# AD637-.net
KiCad netlist of a schematic drawn in Altium Designer
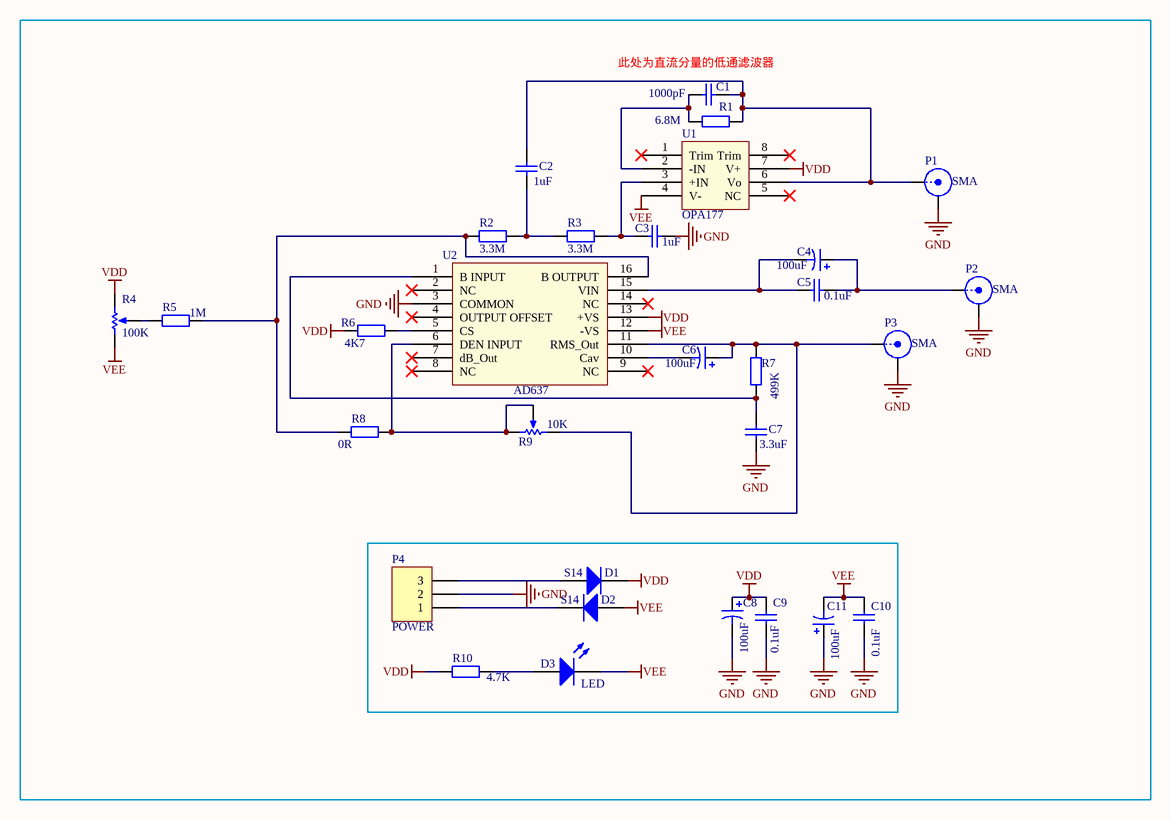
[diagram p0: AD637-有效值检测新版.SchDoc]

(export (version "E")
  (design (tool "Eeschema 10.0.6"))
  (components
    (comp (ref "C1")
      (value "1000pF")
      (footprint "common:C0805")
      (description "Capacitor")
      (fields (field (name "PUBLISHER") "Altium Limited"))
      (libsource (lib "Miscellaneous Devices") (part "Cap"))
    )
    (comp (ref "C2")
      (value "1uF")
      (footprint "common:C0805")
      (description "Capacitor")
      (fields (field (name "PUBLISHER") "Altium Limited"))
      (libsource (lib "Miscellaneous Devices") (part "Cap"))
    )
    (comp (ref "C3")
      (value "1uF")
      (footprint "common:C0805")
      (description "Capacitor")
      (fields (field (name "PUBLISHER") "Altium Limited"))
      (libsource (lib "Miscellaneous Devices") (part "Cap"))
    )
    (comp (ref "C4")
      (value "100uF")
      (footprint "common:C7343")
      (description "Polarized Capacitor (Radial)")
      (fields (field (name "PUBLISHER") "Altium Limited"))
      (libsource (lib "Miscellaneous Devices") (part "Cap Pol1"))
    )
    (comp (ref "C5")
      (value "0.1uF")
      (footprint "common:C0805")
      (description "Capacitor")
      (fields (field (name "PUBLISHER") "Altium Limited"))
      (libsource (lib "Miscellaneous Devices") (part "Cap"))
    )
    (comp (ref "C6")
      (value "100uF")
      (footprint "common:C7343")
      (description "Polarized Capacitor (Radial)")
      (fields (field (name "PUBLISHER") "Altium Limited"))
      (libsource (lib "Miscellaneous Devices") (part "Cap Pol1"))
    )
    (comp (ref "C7")
      (value "3.3uF")
      (footprint "common:C0805")
      (description "Capacitor")
      (fields (field (name "PUBLISHER") "Altium Limited"))
      (libsource (lib "Miscellaneous Devices") (part "Cap"))
    )
    (comp (ref "C8")
      (value "100uF")
      (footprint "common:C7343")
      (description "Polarized Capacitor (Radial)")
      (fields (field (name "PUBLISHER") "Altium Limited"))
      (libsource (lib "Miscellaneous Devices") (part "Cap Pol1"))
    )
    (comp (ref "C9")
      (value "0.1uF")
      (footprint "common:C0805")
      (description "Capacitor")
      (fields (field (name "PUBLISHER") "Altium Limited"))
      (libsource (lib "Miscellaneous Devices") (part "Cap"))
    )
    (comp (ref "C10")
      (value "0.1uF")
      (footprint "common:C0805")
      (description "Capacitor")
      (fields (field (name "PUBLISHER") "Altium Limited"))
      (libsource (lib "Miscellaneous Devices") (part "Cap"))
    )
    (comp (ref "C11")
      (value "100uF")
      (footprint "common:C7343")
      (description "Polarized Capacitor (Radial)")
      (fields (field (name "PUBLISHER") "Altium Limited"))
      (libsource (lib "Miscellaneous Devices") (part "Cap Pol1"))
    )
    (comp (ref "D1")
      (value "S14")
      (footprint "common:SOD123")
      (description "1 Amp General Purpose Rectifier")
      (fields (field (name "PUBLISHER") "Altium Limited"))
      (libsource (lib "Miscellaneous Devices") (part "Diode 1N4007"))
    )
    (comp (ref "D2")
      (value "S14")
      (footprint "common:SOD123")
      (description "1 Amp General Purpose Rectifier")
      (fields (field (name "PUBLISHER") "Altium Limited"))
      (libsource (lib "Miscellaneous Devices") (part "Diode 1N4007"))
    )
    (comp (ref "D3")
      (value "LED")
      (footprint "common:LED0805R")
      (fields (field (name "PUBLISHER") "Altium Limited"))
      (libsource (lib "Xiaowei") (part "LED"))
    )
    (comp (ref "P1")
      (value "SMA")
      (footprint "Xiaowei:SM")
      (description "BNC Elbow Connector")
      (fields (field (name "PUBLISHER") "Altium Limited"))
      (libsource (lib "Miscellaneous Connectors") (part "BNC"))
    )
    (comp (ref "P2")
      (value "SMA")
      (footprint "Xiaowei:SM")
      (description "BNC Elbow Connector")
      (fields (field (name "PUBLISHER") "Altium Limited"))
      (libsource (lib "Miscellaneous Connectors") (part "BNC"))
    )
    (comp (ref "P3")
      (value "SMA")
      (footprint "Xiaowei:SM")
      (description "BNC Elbow Connector")
      (fields (field (name "PUBLISHER") "Altium Limited"))
      (libsource (lib "Miscellaneous Connectors") (part "BNC"))
    )
    (comp (ref "P4")
      (value "POWER")
      (footprint "common:3PIN-5.08B")
      (description "Header, 3-Pin")
      (fields (field (name "PUBLISHER") "Altium Limited"))
      (libsource (lib "Xiaowei") (part "Header 3"))
    )
    (comp (ref "R1")
      (value "6.8M")
      (footprint "common:R0805")
      (description "Resistor")
      (fields (field (name "PUBLISHER") "Altium Limited"))
      (libsource (lib "Miscellaneous Devices") (part "Res2"))
    )
    (comp (ref "R2")
      (value "3.3M")
      (footprint "common:R0805")
      (description "Resistor")
      (fields (field (name "PUBLISHER") "Altium Limited"))
      (libsource (lib "Miscellaneous Devices") (part "Res2"))
    )
    (comp (ref "R3")
      (value "3.3M")
      (footprint "common:R0805")
      (description "Resistor")
      (fields (field (name "PUBLISHER") "Altium Limited"))
      (libsource (lib "Miscellaneous Devices") (part "Res2"))
    )
    (comp (ref "R4")
      (value "100K")
      (footprint "common:3296W")
      (description "Potentiometer")
      (fields (field (name "PUBLISHER") "Altium Limited"))
      (libsource (lib "Miscellaneous Devices") (part "RPot"))
    )
    (comp (ref "R5")
      (value "1M")
      (footprint "common:R0805")
      (description "Resistor")
      (fields (field (name "PUBLISHER") "Altium Limited"))
      (libsource (lib "Miscellaneous Devices") (part "Res2"))
    )
    (comp (ref "R6")
      (value "4K7")
      (footprint "common:R0805")
      (description "Resistor")
      (fields (field (name "PUBLISHER") "Altium Limited"))
      (libsource (lib "Miscellaneous Devices") (part "Res2"))
    )
    (comp (ref "R7")
      (value "499K")
      (footprint "common:R0805")
      (description "Resistor")
      (fields (field (name "PUBLISHER") "Altium Limited"))
      (libsource (lib "") (part "Res2_1"))
    )
    (comp (ref "R8")
      (value "0R")
      (footprint "common:R0805")
      (description "Resistor")
      (fields (field (name "PUBLISHER") "Altium Limited"))
      (libsource (lib "Miscellaneous Devices") (part "Res2"))
    )
    (comp (ref "R9")
      (value "10K")
      (footprint "common:3296W")
      (description "Potentiometer")
      (fields (field (name "PUBLISHER") "Altium Limited"))
      (libsource (lib "Miscellaneous Devices") (part "RPot"))
    )
    (comp (ref "R10")
      (value "4.7K")
      (footprint "common:R0805")
      (description "Resistor")
      (fields (field (name "PUBLISHER") "Altium Limited"))
      (libsource (lib "Miscellaneous Devices") (part "Res2"))
    )
    (comp (ref "U1") (value "OPA177") (footprint "common:SOP8") (libsource (lib "Xiaowei") (part "OPA177")))
    (comp (ref "U2") (value "AD637") (footprint "Xiaowei:AD637") (libsource (lib "Xiaowei") (part "AD637")))
  )
  (nets
    (net (code "1") (name "GND") (class "Default")
      (node (ref "C10") (pin "1") (pinfunction "1_1") (pintype "passive"))
      (node (ref "C11") (pin "1") (pinfunction "1_1") (pintype "passive"))
      (node (ref "C3") (pin "1") (pinfunction "1_1") (pintype "passive"))
      (node (ref "C7") (pin "1") (pinfunction "1_1") (pintype "passive"))
      (node (ref "C8") (pin "2") (pinfunction "2_2") (pintype "passive"))
      (node (ref "C9") (pin "1") (pinfunction "1_1") (pintype "passive"))
      (node (ref "P1") (pin "2") (pinfunction "Y_2") (pintype "passive"))
      (node (ref "P2") (pin "2") (pinfunction "Y_2") (pintype "passive"))
      (node (ref "P3") (pin "2") (pinfunction "Y_2") (pintype "passive"))
      (node (ref "P4") (pin "2") (pinfunction "2_2") (pintype "passive"))
      (node (ref "U2") (pin "3") (pinfunction "COMMON_3") (pintype "passive"))
    )
    (net (code "2") (name "Net-(C2-Pad2)") (class "Default")
      (node (ref "C2") (pin "2") (pinfunction "2_2") (pintype "passive"))
      (node (ref "R2") (pin "2") (pinfunction "2_2") (pintype "passive"))
      (node (ref "R3") (pin "1") (pinfunction "1_1") (pintype "passive"))
    )
    (net (code "3") (name "Net-(D1-A)") (class "Default")
      (node (ref "D1") (pin "1") (pinfunction "A_1") (pintype "passive"))
      (node (ref "P4") (pin "3") (pinfunction "3_3") (pintype "passive"))
    )
    (net (code "4") (name "Net-(D2-K)") (class "Default")
      (node (ref "D2") (pin "2") (pinfunction "K_2") (pintype "passive"))
      (node (ref "P4") (pin "1") (pinfunction "1_1") (pintype "passive"))
    )
    (net (code "5") (name "Net-(D3-Pad1)") (class "Default")
      (node (ref "D3") (pin "1") (pinfunction "1_1") (pintype "passive"))
      (node (ref "R10") (pin "2") (pinfunction "2_2") (pintype "passive"))
    )
    (net (code "6") (name "Net-(P1-X)") (class "Default")
      (node (ref "C1") (pin "1") (pinfunction "1_1") (pintype "passive"))
      (node (ref "C2") (pin "1") (pinfunction "1_1") (pintype "passive"))
      (node (ref "P1") (pin "1") (pinfunction "X_1") (pintype "passive"))
      (node (ref "R1") (pin "2") (pinfunction "2_2") (pintype "passive"))
      (node (ref "U1") (pin "6") (pinfunction "Vo_6") (pintype "passive"))
    )
    (net (code "7") (name "Net-(P2-X)") (class "Default")
      (node (ref "C4") (pin "1") (pinfunction "1_1") (pintype "passive"))
      (node (ref "C5") (pin "1") (pinfunction "1_1") (pintype "passive"))
      (node (ref "P2") (pin "1") (pinfunction "X_1") (pintype "passive"))
    )
    (net (code "8") (name "Net-(P3-X)") (class "Default")
      (node (ref "C6") (pin "1") (pinfunction "1_1") (pintype "passive"))
      (node (ref "P3") (pin "1") (pinfunction "X_1") (pintype "passive"))
      (node (ref "R7") (pin "2") (pinfunction "2_2") (pintype "passive"))
      (node (ref "R9") (pin "1") (pinfunction "TOP_1") (pintype "passive"))
      (node (ref "U2") (pin "11") (pinfunction "RMS_Out_11") (pintype "passive"))
    )
    (net (code "9") (name "Net-(R4-TAP)") (class "Default")
      (node (ref "R4") (pin "3") (pinfunction "TAP_3") (pintype "passive"))
      (node (ref "R5") (pin "1") (pinfunction "1_1") (pintype "passive"))
    )
    (net (code "10") (name "Net-(R9-BOT)") (class "Default")
      (node (ref "R8") (pin "2") (pinfunction "2_2") (pintype "passive"))
      (node (ref "R9") (pin "2") (pinfunction "BOT_2") (pintype "passive"))
      (node (ref "R9") (pin "3") (pinfunction "TAP_3") (pintype "passive"))
      (node (ref "U2") (pin "6") (pinfunction "DEN_INPUT_6") (pintype "passive"))
    )
    (net (code "11") (name "Net-(U1-+IN)") (class "Default")
      (node (ref "C3") (pin "2") (pinfunction "2_2") (pintype "passive"))
      (node (ref "R3") (pin "2") (pinfunction "2_2") (pintype "passive"))
      (node (ref "U1") (pin "3") (pinfunction "+IN_3") (pintype "passive"))
    )
    (net (code "12") (name "Net-(U1--IN)") (class "Default")
      (node (ref "C1") (pin "2") (pinfunction "2_2") (pintype "passive"))
      (node (ref "R1") (pin "1") (pinfunction "1_1") (pintype "passive"))
      (node (ref "U1") (pin "2") (pinfunction "-IN_2") (pintype "passive"))
    )
    (net (code "13") (name "Net-(U2-B_INPUT)") (class "Default")
      (node (ref "C7") (pin "2") (pinfunction "2_2") (pintype "passive"))
      (node (ref "R7") (pin "1") (pinfunction "1_1") (pintype "passive"))
      (node (ref "U2") (pin "1") (pinfunction "B_INPUT_1") (pintype "passive"))
    )
    (net (code "14") (name "Net-(U2-B_OUTPUT)") (class "Default")
      (node (ref "R2") (pin "1") (pinfunction "1_1") (pintype "passive"))
      (node (ref "R5") (pin "2") (pinfunction "2_2") (pintype "passive"))
      (node (ref "R8") (pin "1") (pinfunction "1_1") (pintype "passive"))
      (node (ref "U2") (pin "16") (pinfunction "B_OUTPUT_16") (pintype "passive"))
    )
    (net (code "15") (name "Net-(U2-CS)") (class "Default")
      (node (ref "R6") (pin "2") (pinfunction "2_2") (pintype "passive"))
      (node (ref "U2") (pin "5") (pinfunction "CS_5") (pintype "passive"))
    )
    (net (code "16") (name "Net-(U2-Cav)") (class "Default")
      (node (ref "C6") (pin "2") (pinfunction "2_2") (pintype "passive"))
      (node (ref "U2") (pin "10") (pinfunction "Cav_10") (pintype "passive"))
    )
    (net (code "17") (name "Net-(U2-VIN)") (class "Default")
      (node (ref "C4") (pin "2") (pinfunction "2_2") (pintype "passive"))
      (node (ref "C5") (pin "2") (pinfunction "2_2") (pintype "passive"))
      (node (ref "U2") (pin "15") (pinfunction "VIN_15") (pintype "passive"))
    )
    (net (code "18") (name "VDD") (class "Default")
      (node (ref "C8") (pin "1") (pinfunction "1_1") (pintype "passive"))
      (node (ref "C9") (pin "2") (pinfunction "2_2") (pintype "passive"))
      (node (ref "D1") (pin "2") (pinfunction "K_2") (pintype "passive"))
      (node (ref "R10") (pin "1") (pinfunction "1_1") (pintype "passive"))
      (node (ref "R4") (pin "2") (pinfunction "BOT_2") (pintype "passive"))
      (node (ref "R6") (pin "1") (pinfunction "1_1") (pintype "passive"))
      (node (ref "U1") (pin "7") (pinfunction "V+_7") (pintype "passive"))
      (node (ref "U2") (pin "13") (pinfunction "+VS_13") (pintype "passive"))
    )
    (net (code "19") (name "VEE") (class "Default")
      (node (ref "C10") (pin "2") (pinfunction "2_2") (pintype "passive"))
      (node (ref "C11") (pin "2") (pinfunction "2_2") (pintype "passive"))
      (node (ref "D2") (pin "1") (pinfunction "A_1") (pintype "passive"))
      (node (ref "D3") (pin "2") (pinfunction "2_2") (pintype "passive"))
      (node (ref "R4") (pin "1") (pinfunction "TOP_1") (pintype "passive"))
      (node (ref "U1") (pin "4") (pinfunction "V-_4") (pintype "passive"))
      (node (ref "U2") (pin "12") (pinfunction "-VS_12") (pintype "passive"))
    )
    (net (code "20") (name "unconnected-(U1-NC-Pad5)") (class "Default")
      (node (ref "U1") (pin "5") (pinfunction "NC_5") (pintype "passive+no_connect"))
    )
    (net (code "21") (name "unconnected-(U1-Trim-Pad1)") (class "Default")
      (node (ref "U1") (pin "1") (pinfunction "Trim_1") (pintype "passive+no_connect"))
    )
    (net (code "22") (name "unconnected-(U1-Trim-Pad8)") (class "Default")
      (node (ref "U1") (pin "8") (pinfunction "Trim_8") (pintype "passive+no_connect"))
    )
    (net (code "23") (name "unconnected-(U2-NC-Pad2)") (class "Default")
      (node (ref "U2") (pin "2") (pinfunction "NC_2") (pintype "passive+no_connect"))
    )
    (net (code "24") (name "unconnected-(U2-NC-Pad8)") (class "Default")
      (node (ref "U2") (pin "8") (pinfunction "NC_8") (pintype "passive+no_connect"))
    )
    (net (code "25") (name "unconnected-(U2-NC-Pad9)") (class "Default")
      (node (ref "U2") (pin "9") (pinfunction "NC_9") (pintype "passive+no_connect"))
    )
    (net (code "26") (name "unconnected-(U2-NC-Pad14)") (class "Default")
      (node (ref "U2") (pin "14") (pinfunction "NC_14") (pintype "passive+no_connect"))
    )
    (net (code "27") (name "unconnected-(U2-OUTPUT_OFFSET-Pad4)") (class "Default")
      (node (ref "U2") (pin "4") (pinfunction "OUTPUT_OFFSET_4") (pintype "passive+no_connect"))
    )
    (net (code "28") (name "unconnected-(U2-dB_Out-Pad7)") (class "Default")
      (node (ref "U2") (pin "7") (pinfunction "dB_Out_7") (pintype "passive+no_connect"))
    )
  )
)
